# Sheet.net
KiCad netlist of a schematic drawn in Altium Designer
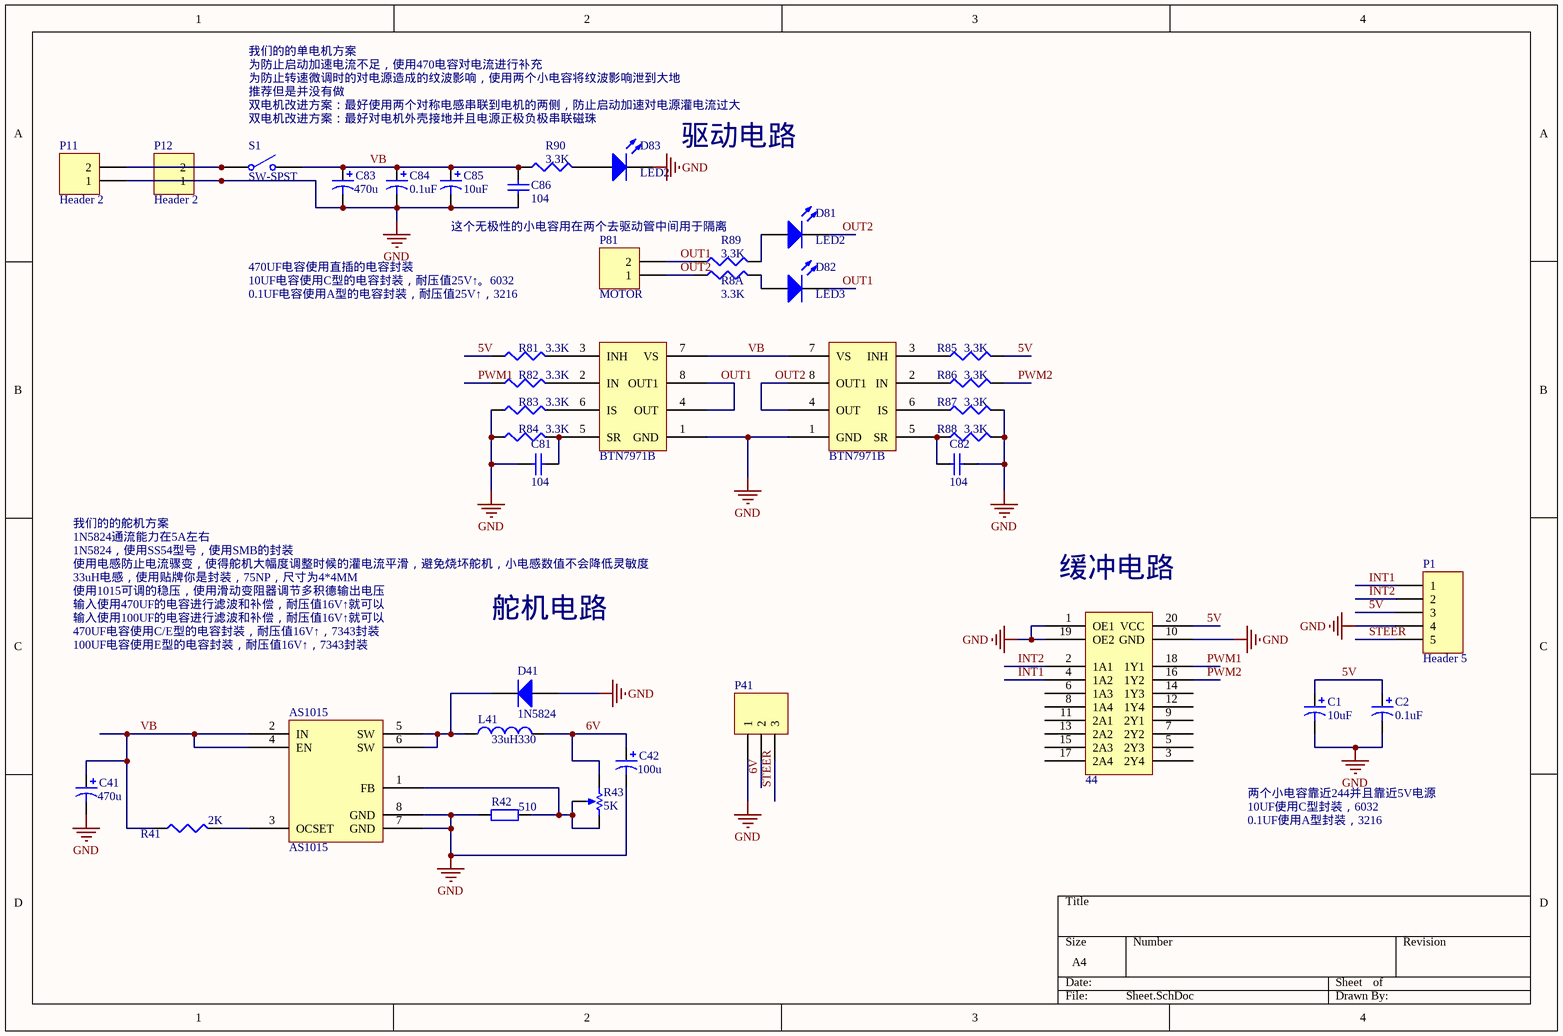
[diagram p0: Sheet.SchDoc]

(export (version "E")
  (design (tool "Eeschema 10.0.6"))
  (components
    (comp (ref "1B-1")
      (value "BTN7971B")
      (footprint "BTN7971B")
      (description "TO-263")
      (libsource (lib "ALL") (part "BTN9791B"))
    )
    (comp (ref "1B-2") (value "BTN7971B") (footprint "BTN7971B") (libsource (lib "ALL") (part "BTN7971B")))
    (comp (ref "AS1015") (value "AS1015") (footprint "SOP-8N") (libsource (lib "vehicle") (part "AS1015")))
    (comp (ref "C1")
      (value "10uF")
      (footprint "C6032")
      (description "Polarized Capacitor (Surface Mount)")
      (fields (field (name "Comment") "Cap Pol3") (field (name "PUBLISHER") "Altium Limited"))
      (libsource (lib "Miscellaneous Devices") (part "Cap Pol3"))
    )
    (comp (ref "C2")
      (value "0.1uF")
      (footprint "C3216")
      (description "Polarized Capacitor (Surface Mount)")
      (fields (field (name "Comment") "Cap Pol3") (field (name "PUBLISHER") "Altium Limited"))
      (libsource (lib "Miscellaneous Devices") (part "Cap Pol3"))
    )
    (comp (ref "C41")
      (value "470u")
      (footprint "C7343")
      (description "Polarized Capacitor (Surface Mount)")
      (fields (field (name "Comment") "Cap Pol3") (field (name "PUBLISHER") "Altium Limited"))
      (libsource (lib "Miscellaneous Devices") (part "Cap Pol3"))
    )
    (comp (ref "C42")
      (value "100u")
      (footprint "C6032")
      (description "Polarized Capacitor (Surface Mount)")
      (fields (field (name "Comment") "Cap Pol3") (field (name "PUBLISHER") "Altium Limited"))
      (libsource (lib "Miscellaneous Devices") (part "Cap Pol3"))
    )
    (comp (ref "C81")
      (value "104")
      (footprint "C0805")
      (description "Polarized Capacitor (Radial)")
      (fields (field (name "Comment") "Cap Chip 0805") (field (name "PUBLISHER") "Altium Limited"))
      (libsource (lib "电容") (part "Cap Chip 0805"))
    )
    (comp (ref "C82")
      (value "104")
      (footprint "C0805")
      (description "Polarized Capacitor (Radial)")
      (fields (field (name "Comment") "Cap Chip 0805") (field (name "PUBLISHER") "Altium Limited"))
      (libsource (lib "电容") (part "Cap Chip 0805"))
    )
    (comp (ref "C83")
      (value "470u")
      (footprint "CAPPR5-8X11.5")
      (description "Polarized Capacitor (Surface Mount)")
      (fields (field (name "Comment") "Cap Pol3") (field (name "PUBLISHER") "Altium Limited"))
      (libsource (lib "Miscellaneous Devices") (part "Cap Pol3"))
    )
    (comp (ref "C84")
      (value "0.1uF")
      (footprint "C3216")
      (description "Polarized Capacitor (Surface Mount)")
      (fields (field (name "Comment") "Cap Pol3") (field (name "PUBLISHER") "Altium Limited"))
      (libsource (lib "Miscellaneous Devices") (part "Cap Pol3"))
    )
    (comp (ref "C85")
      (value "10uF")
      (footprint "C6032")
      (description "Polarized Capacitor (Surface Mount)")
      (fields (field (name "Comment") "Cap Pol3") (field (name "PUBLISHER") "Altium Limited"))
      (libsource (lib "Miscellaneous Devices") (part "Cap Pol3"))
    )
    (comp (ref "C86")
      (value "104")
      (footprint "C0805")
      (description "Polarized Capacitor (Radial)")
      (fields (field (name "Comment") "Cap Chip 0805") (field (name "PUBLISHER") "Altium Limited"))
      (libsource (lib "电容") (part "Cap Chip 0805"))
    )
    (comp (ref "D41")
      (value "1N5824")
      (footprint "SMB")
      (description "1.0 Ampere General Purpose Rectifier")
      (fields (field (name "PUBLISHER") "Altium Limited"))
      (libsource (lib "FSC Discrete Rectifier") (part "1N4007"))
    )
    (comp (ref "D81")
      (value "LED2")
      (footprint "SOD-123")
      (description "Typical BLUE SiC LED")
      (fields (field (name "PUBLISHER") "Altium Limited"))
      (libsource (lib "Miscellaneous Devices") (part "LED3"))
    )
    (comp (ref "D82")
      (value "LED3")
      (footprint "SOD-123")
      (description "Typical BLUE SiC LED")
      (fields (field (name "PUBLISHER") "Altium Limited"))
      (libsource (lib "Miscellaneous Devices") (part "LED3"))
    )
    (comp (ref "D83")
      (value "LED2")
      (footprint "C1206")
      (description "Typical BLUE SiC LED")
      (fields (field (name "PUBLISHER") "Altium Limited"))
      (libsource (lib "Miscellaneous Devices") (part "LED3"))
    )
    (comp (ref "L41")
      (value "33uH330")
      (footprint "CD75NP")
      (description "Inductor")
      (fields (field (name "PUBLISHER") "Altium Limited"))
      (libsource (lib "Miscellaneous Devices") (part "Inductor"))
    )
    (comp (ref "P1")
      (value "Header 5")
      (footprint "连接器:HDR1X5")
      (description "Header, 5-Pin")
      (fields (field (name "PUBLISHER") "Altium Limited"))
      (libsource (lib "连接器") (part "Header 5"))
    )
    (comp (ref "P11")
      (value "Header 2")
      (footprint "2PIN-5.08A")
      (description "Header, 2-Pin")
      (fields (field (name "PUBLISHER") "Altium Limited"))
      (libsource (lib "连接器") (part "Header 2"))
    )
    (comp (ref "P12")
      (value "Header 2")
      (footprint "T_Plug")
      (description "Header, 2-Pin")
      (fields (field (name "PUBLISHER") "Altium Limited"))
      (libsource (lib "连接器") (part "Header 2"))
    )
    (comp (ref "P41")
      (value "Header 3")
      (footprint "HDR1X3")
      (description "Header, 3-Pin")
      (fields (field (name "PUBLISHER") "Altium Limited"))
      (libsource (lib "Miscellaneous Connectors") (part "Header 3"))
    )
    (comp (ref "P81")
      (value "MOTOR")
      (footprint "5.08-2P")
      (description "Header, 2-Pin")
      (fields (field (name "PUBLISHER") "Altium Limited"))
      (libsource (lib "Miscellaneous Connectors") (part "Header 2"))
    )
    (comp (ref "R8A")
      (value "3.3K")
      (footprint "R0805")
      (description "Resistor")
      (fields (field (name "PUBLISHER") "Altium Limited"))
      (libsource (lib "Miscellaneous Devices") (part "Res3"))
    )
    (comp (ref "R41")
      (value "2K")
      (footprint "R0805")
      (description "Resistor")
      (fields (field (name "Comment") "Res3") (field (name "PUBLISHER") "Altium Limited"))
      (libsource (lib "Miscellaneous Devices") (part "Res3"))
    )
    (comp (ref "R42")
      (value "510")
      (footprint "R0805")
      (description "Resistor")
      (fields (field (name "Comment") "Res2") (field (name "PUBLISHER") "Altium Limited"))
      (libsource (lib "Miscellaneous Devices") (part "Res2"))
    )
    (comp (ref "R43")
      (value "5K")
      (footprint "VR_B1")
      (description "精密可调电阻")
      (fields (field (name "Comment") "RPot") (field (name "PUBLISHER") "Altium Limited"))
      (libsource (lib "32mini") (part "RPot"))
    )
    (comp (ref "R81")
      (value "3.3K")
      (footprint "R0805")
      (description "Resistor")
      (fields (field (name "PUBLISHER") "Altium Limited"))
      (libsource (lib "Miscellaneous Devices") (part "Res3"))
    )
    (comp (ref "R82")
      (value "3.3K")
      (footprint "R0805")
      (description "Resistor")
      (fields (field (name "PUBLISHER") "Altium Limited"))
      (libsource (lib "Miscellaneous Devices") (part "Res3"))
    )
    (comp (ref "R83")
      (value "3.3K")
      (footprint "R0805")
      (description "Resistor")
      (fields (field (name "PUBLISHER") "Altium Limited"))
      (libsource (lib "Miscellaneous Devices") (part "Res3"))
    )
    (comp (ref "R84")
      (value "3.3K")
      (footprint "R0805")
      (description "Resistor")
      (fields (field (name "PUBLISHER") "Altium Limited"))
      (libsource (lib "Miscellaneous Devices") (part "Res3"))
    )
    (comp (ref "R85")
      (value "3.3K")
      (footprint "R0805")
      (description "Resistor")
      (fields (field (name "PUBLISHER") "Altium Limited"))
      (libsource (lib "Miscellaneous Devices") (part "Res3"))
    )
    (comp (ref "R86")
      (value "3.3K")
      (footprint "R0805")
      (description "Resistor")
      (fields (field (name "PUBLISHER") "Altium Limited"))
      (libsource (lib "Miscellaneous Devices") (part "Res3"))
    )
    (comp (ref "R87")
      (value "3.3K")
      (footprint "R0805")
      (description "Resistor")
      (fields (field (name "PUBLISHER") "Altium Limited"))
      (libsource (lib "Miscellaneous Devices") (part "Res3"))
    )
    (comp (ref "R88")
      (value "3.3K")
      (footprint "R0805")
      (description "Resistor")
      (fields (field (name "PUBLISHER") "Altium Limited"))
      (libsource (lib "Miscellaneous Devices") (part "Res3"))
    )
    (comp (ref "R89")
      (value "3.3K")
      (footprint "R0805")
      (description "Resistor")
      (fields (field (name "PUBLISHER") "Altium Limited"))
      (libsource (lib "Miscellaneous Devices") (part "Res3"))
    )
    (comp (ref "R90")
      (value "3.3K")
      (footprint "R0805")
      (description "Resistor")
      (fields (field (name "PUBLISHER") "Altium Limited"))
      (libsource (lib "Miscellaneous Devices") (part "Res3"))
    )
    (comp (ref "S1")
      (value "SW-SPST")
      (footprint "SW-TO3")
      (description "Single-Pole, Single-Throw Switch")
      (fields (field (name "PUBLISHER") "Altium Limited"))
      (libsource (lib "开关按键器件") (part "SW-SPST"))
    )
    (comp (ref "Z")
      (value "44")
      (footprint "SOP20_M")
      (description "SOP-20")
      (libsource (lib "ALL") (part "74LS244"))
    )
  )
  (nets
    (net (code "1") (name "/5V") (class "Default")
      (node (ref "C1") (pin "1") (pinfunction "1_1") (pintype "passive"))
      (node (ref "C2") (pin "1") (pinfunction "1_1") (pintype "passive"))
      (node (ref "P1") (pin "3") (pinfunction "3_3") (pintype "passive"))
      (node (ref "R81") (pin "1") (pinfunction "1_1") (pintype "passive"))
      (node (ref "R85") (pin "2") (pinfunction "2_2") (pintype "passive"))
      (node (ref "Z") (pin "20") (pinfunction "VCC_20") (pintype "passive"))
    )
    (net (code "2") (name "/6V") (class "Default")
      (node (ref "C42") (pin "1") (pinfunction "1_1") (pintype "passive"))
      (node (ref "L41") (pin "2") (pinfunction "2_2") (pintype "passive"))
      (node (ref "P41") (pin "2") (pinfunction "2_2") (pintype "passive"))
      (node (ref "R43") (pin "1") (pinfunction "TOP_1") (pintype "passive"))
    )
    (net (code "3") (name "/INT1") (class "Default")
      (node (ref "P1") (pin "1") (pinfunction "1_1") (pintype "passive"))
      (node (ref "Z") (pin "4") (pinfunction "1A2_4") (pintype "passive"))
    )
    (net (code "4") (name "/INT2") (class "Default")
      (node (ref "P1") (pin "2") (pinfunction "2_2") (pintype "passive"))
      (node (ref "Z") (pin "2") (pinfunction "1A1_2") (pintype "passive"))
    )
    (net (code "5") (name "/OUT1") (class "Default")
      (node (ref "1B-1") (pin "4") (pinfunction "OUT_4") (pintype "passive"))
      (node (ref "1B-1") (pin "8") (pinfunction "OUT1_8") (pintype "passive"))
      (node (ref "D82") (pin "2") (pinfunction "K_2") (pintype "passive"))
      (node (ref "P81") (pin "2") (pinfunction "2_2") (pintype "passive"))
      (node (ref "R89") (pin "1") (pinfunction "1_1") (pintype "passive"))
    )
    (net (code "6") (name "/OUT2") (class "Default")
      (node (ref "1B-2") (pin "4") (pinfunction "OUT_4") (pintype "passive"))
      (node (ref "1B-2") (pin "8") (pinfunction "OUT1_8") (pintype "passive"))
      (node (ref "D81") (pin "2") (pinfunction "K_2") (pintype "passive"))
      (node (ref "P81") (pin "1") (pinfunction "1_1") (pintype "passive"))
      (node (ref "R8A") (pin "1") (pinfunction "1_1") (pintype "passive"))
    )
    (net (code "7") (name "/PWM1") (class "Default")
      (node (ref "R82") (pin "1") (pinfunction "1_1") (pintype "passive"))
      (node (ref "Z") (pin "18") (pinfunction "1Y1_18") (pintype "passive"))
    )
    (net (code "8") (name "/PWM2") (class "Default")
      (node (ref "R86") (pin "2") (pinfunction "2_2") (pintype "passive"))
      (node (ref "Z") (pin "16") (pinfunction "1Y2_16") (pintype "passive"))
    )
    (net (code "9") (name "/STEER") (class "Default")
      (node (ref "P1") (pin "5") (pinfunction "5_5") (pintype "passive"))
      (node (ref "P41") (pin "3") (pinfunction "3_3") (pintype "passive"))
    )
    (net (code "10") (name "/VB") (class "Default")
      (node (ref "1B-1") (pin "7") (pinfunction "VS_7") (pintype "passive"))
      (node (ref "1B-2") (pin "7") (pinfunction "VS_7") (pintype "passive"))
      (node (ref "AS1015") (pin "2") (pinfunction "IN_2") (pintype "passive"))
      (node (ref "AS1015") (pin "4") (pinfunction "EN_4") (pintype "passive"))
      (node (ref "C41") (pin "1") (pinfunction "1_1") (pintype "passive"))
      (node (ref "C83") (pin "1") (pinfunction "1_1") (pintype "passive"))
      (node (ref "C84") (pin "1") (pinfunction "1_1") (pintype "passive"))
      (node (ref "C85") (pin "1") (pinfunction "1_1") (pintype "passive"))
      (node (ref "C86") (pin "2") (pinfunction "2_2") (pintype "passive"))
      (node (ref "R41") (pin "1") (pinfunction "1_1") (pintype "passive"))
      (node (ref "R90") (pin "1") (pinfunction "1_1") (pintype "passive"))
      (node (ref "S1") (pin "2") (pinfunction "NO_2") (pintype "passive"))
    )
    (net (code "11") (name "GND") (class "Default")
      (node (ref "1B-1") (pin "1") (pinfunction "GND_1") (pintype "passive"))
      (node (ref "1B-2") (pin "1") (pinfunction "GND_1") (pintype "passive"))
      (node (ref "AS1015") (pin "7") (pinfunction "GND_7") (pintype "passive"))
      (node (ref "AS1015") (pin "8") (pinfunction "GND_8") (pintype "passive"))
      (node (ref "C1") (pin "2") (pinfunction "2_2") (pintype "passive"))
      (node (ref "C2") (pin "2") (pinfunction "2_2") (pintype "passive"))
      (node (ref "C41") (pin "2") (pinfunction "2_2") (pintype "passive"))
      (node (ref "C42") (pin "2") (pinfunction "2_2") (pintype "passive"))
      (node (ref "C81") (pin "1") (pinfunction "1_1") (pintype "passive"))
      (node (ref "C82") (pin "2") (pinfunction "2_2") (pintype "passive"))
      (node (ref "C83") (pin "2") (pinfunction "2_2") (pintype "passive"))
      (node (ref "C84") (pin "2") (pinfunction "2_2") (pintype "passive"))
      (node (ref "C85") (pin "2") (pinfunction "2_2") (pintype "passive"))
      (node (ref "C86") (pin "1") (pinfunction "1_1") (pintype "passive"))
      (node (ref "D41") (pin "1") (pinfunction "A_1") (pintype "passive"))
      (node (ref "D83") (pin "2") (pinfunction "K_2") (pintype "passive"))
      (node (ref "P1") (pin "4") (pinfunction "4_4") (pintype "passive"))
      (node (ref "P11") (pin "1") (pinfunction "1_1") (pintype "passive"))
      (node (ref "P12") (pin "1") (pinfunction "1_1") (pintype "passive"))
      (node (ref "P41") (pin "1") (pinfunction "1_1") (pintype "passive"))
      (node (ref "R42") (pin "1") (pinfunction "1_1") (pintype "passive"))
      (node (ref "R83") (pin "1") (pinfunction "1_1") (pintype "passive"))
      (node (ref "R84") (pin "1") (pinfunction "1_1") (pintype "passive"))
      (node (ref "R87") (pin "2") (pinfunction "2_2") (pintype "passive"))
      (node (ref "R88") (pin "2") (pinfunction "2_2") (pintype "passive"))
      (node (ref "Z") (pin "1") (pinfunction "OE1_1") (pintype "passive"))
      (node (ref "Z") (pin "10") (pinfunction "GND_10") (pintype "passive"))
      (node (ref "Z") (pin "19") (pinfunction "OE2_19") (pintype "passive"))
    )
    (net (code "12") (name "Net-(1B-1-IN)") (class "Default")
      (node (ref "1B-1") (pin "2") (pinfunction "IN_2") (pintype "passive"))
      (node (ref "R82") (pin "2") (pinfunction "2_2") (pintype "passive"))
    )
    (net (code "13") (name "Net-(1B-1-INH)") (class "Default")
      (node (ref "1B-1") (pin "3") (pinfunction "INH_3") (pintype "passive"))
      (node (ref "R81") (pin "2") (pinfunction "2_2") (pintype "passive"))
    )
    (net (code "14") (name "Net-(1B-1-IS)") (class "Default")
      (node (ref "1B-1") (pin "6") (pinfunction "IS_6") (pintype "passive"))
      (node (ref "R83") (pin "2") (pinfunction "2_2") (pintype "passive"))
    )
    (net (code "15") (name "Net-(1B-1-SR)") (class "Default")
      (node (ref "1B-1") (pin "5") (pinfunction "SR_5") (pintype "passive"))
      (node (ref "C81") (pin "2") (pinfunction "2_2") (pintype "passive"))
      (node (ref "R84") (pin "2") (pinfunction "2_2") (pintype "passive"))
    )
    (net (code "16") (name "Net-(1B-2-IN)") (class "Default")
      (node (ref "1B-2") (pin "2") (pinfunction "IN_2") (pintype "passive"))
      (node (ref "R86") (pin "1") (pinfunction "1_1") (pintype "passive"))
    )
    (net (code "17") (name "Net-(1B-2-INH)") (class "Default")
      (node (ref "1B-2") (pin "3") (pinfunction "INH_3") (pintype "passive"))
      (node (ref "R85") (pin "1") (pinfunction "1_1") (pintype "passive"))
    )
    (net (code "18") (name "Net-(1B-2-IS)") (class "Default")
      (node (ref "1B-2") (pin "6") (pinfunction "IS_6") (pintype "passive"))
      (node (ref "R87") (pin "1") (pinfunction "1_1") (pintype "passive"))
    )
    (net (code "19") (name "Net-(1B-2-SR)") (class "Default")
      (node (ref "1B-2") (pin "5") (pinfunction "SR_5") (pintype "passive"))
      (node (ref "C82") (pin "1") (pinfunction "1_1") (pintype "passive"))
      (node (ref "R88") (pin "1") (pinfunction "1_1") (pintype "passive"))
    )
    (net (code "20") (name "Net-(AS1015-FB)") (class "Default")
      (node (ref "AS1015") (pin "1") (pinfunction "FB_1") (pintype "passive"))
      (node (ref "R42") (pin "2") (pinfunction "2_2") (pintype "passive"))
      (node (ref "R43") (pin "2") (pinfunction "TAP_2") (pintype "passive"))
      (node (ref "R43") (pin "3") (pinfunction "BOT_3") (pintype "passive"))
    )
    (net (code "21") (name "Net-(AS1015-OCSET)") (class "Default")
      (node (ref "AS1015") (pin "3") (pinfunction "OCSET_3") (pintype "passive"))
      (node (ref "R41") (pin "2") (pinfunction "2_2") (pintype "passive"))
    )
    (net (code "22") (name "Net-(D41-K)") (class "Default")
      (node (ref "AS1015") (pin "5") (pinfunction "SW_5") (pintype "passive"))
      (node (ref "AS1015") (pin "6") (pinfunction "SW_6") (pintype "passive"))
      (node (ref "D41") (pin "2") (pinfunction "K_2") (pintype "passive"))
      (node (ref "L41") (pin "1") (pinfunction "1_1") (pintype "passive"))
    )
    (net (code "23") (name "Net-(D81-A)") (class "Default")
      (node (ref "D81") (pin "1") (pinfunction "A_1") (pintype "passive"))
      (node (ref "R89") (pin "2") (pinfunction "2_2") (pintype "passive"))
    )
    (net (code "24") (name "Net-(D82-A)") (class "Default")
      (node (ref "D82") (pin "1") (pinfunction "A_1") (pintype "passive"))
      (node (ref "R8A") (pin "2") (pinfunction "2_2") (pintype "passive"))
    )
    (net (code "25") (name "Net-(D83-A)") (class "Default")
      (node (ref "D83") (pin "1") (pinfunction "A_1") (pintype "passive"))
      (node (ref "R90") (pin "2") (pinfunction "2_2") (pintype "passive"))
    )
    (net (code "26") (name "Net-(S1-COMMON)") (class "Default")
      (node (ref "P11") (pin "2") (pinfunction "2_2") (pintype "passive"))
      (node (ref "P12") (pin "2") (pinfunction "2_2") (pintype "passive"))
      (node (ref "S1") (pin "1") (pinfunction "COMMON_1") (pintype "passive"))
    )
    (net (code "27") (name "unconnected-(Z-1A3-Pad6)") (class "Default")
      (node (ref "Z") (pin "6") (pinfunction "1A3_6") (pintype "passive"))
    )
    (net (code "28") (name "unconnected-(Z-1A4-Pad8)") (class "Default")
      (node (ref "Z") (pin "8") (pinfunction "1A4_8") (pintype "passive"))
    )
    (net (code "29") (name "unconnected-(Z-1Y3-Pad14)") (class "Default")
      (node (ref "Z") (pin "14") (pinfunction "1Y3_14") (pintype "passive"))
    )
    (net (code "30") (name "unconnected-(Z-1Y4-Pad12)") (class "Default")
      (node (ref "Z") (pin "12") (pinfunction "1Y4_12") (pintype "passive"))
    )
    (net (code "31") (name "unconnected-(Z-2A1-Pad11)") (class "Default")
      (node (ref "Z") (pin "11") (pinfunction "2A1_11") (pintype "passive"))
    )
    (net (code "32") (name "unconnected-(Z-2A2-Pad13)") (class "Default")
      (node (ref "Z") (pin "13") (pinfunction "2A2_13") (pintype "passive"))
    )
    (net (code "33") (name "unconnected-(Z-2A3-Pad15)") (class "Default")
      (node (ref "Z") (pin "15") (pinfunction "2A3_15") (pintype "passive"))
    )
    (net (code "34") (name "unconnected-(Z-2A4-Pad17)") (class "Default")
      (node (ref "Z") (pin "17") (pinfunction "2A4_17") (pintype "passive"))
    )
    (net (code "35") (name "unconnected-(Z-2Y1-Pad9)") (class "Default")
      (node (ref "Z") (pin "9") (pinfunction "2Y1_9") (pintype "passive"))
    )
    (net (code "36") (name "unconnected-(Z-2Y2-Pad7)") (class "Default")
      (node (ref "Z") (pin "7") (pinfunction "2Y2_7") (pintype "passive"))
    )
    (net (code "37") (name "unconnected-(Z-2Y3-Pad5)") (class "Default")
      (node (ref "Z") (pin "5") (pinfunction "2Y3_5") (pintype "passive"))
    )
    (net (code "38") (name "unconnected-(Z-2Y4-Pad3)") (class "Default")
      (node (ref "Z") (pin "3") (pinfunction "2Y4_3") (pintype "passive"))
    )
  )
)
